# gps.net
KiCad netlist of a schematic drawn in Altium Designer
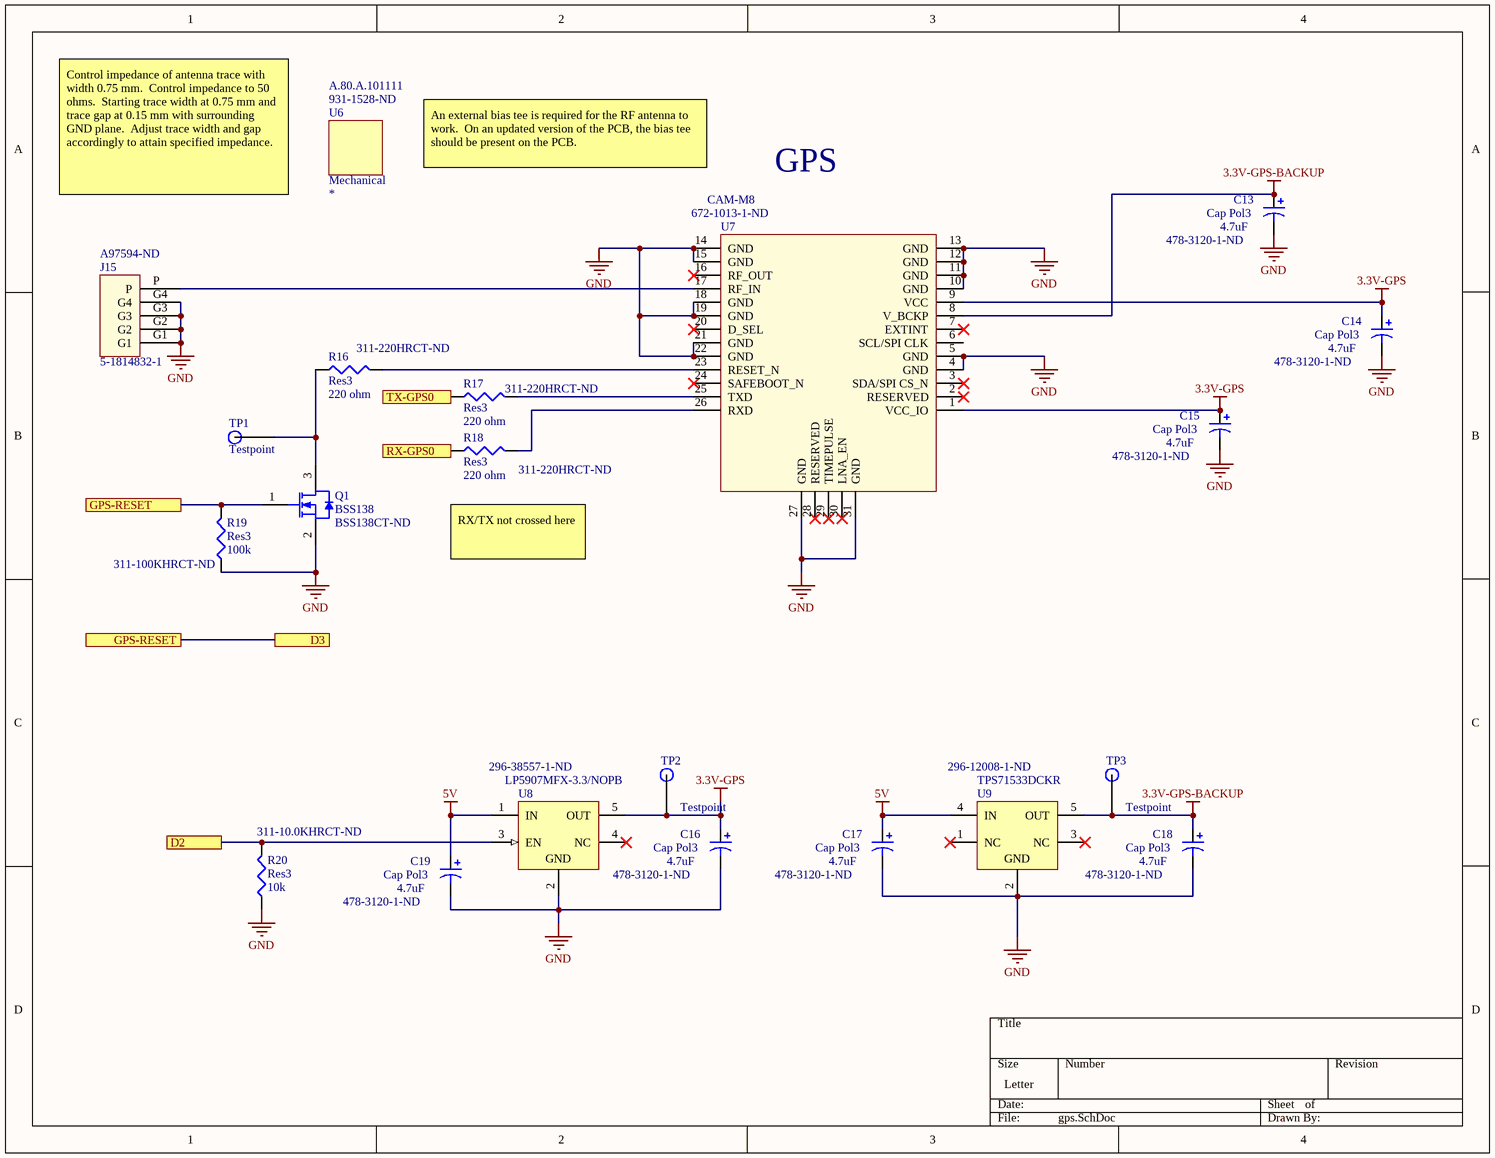
[diagram p0: gps.SchDoc]

(export (version "E")
  (design (tool "Eeschema 10.0.6"))
  (components
    (comp (ref "C13")
      (value "Cap Pol3")
      (footprint "1206-pol")
      (description "Polarized Capacitor (Surface Mount)")
      (fields
        (field (name "ALTIUM_VALUE") "4.7uF")
        (field (name "SUPPLIER PART NUMBER 1") "478-3120-1-ND")
        (field (name "MANUFACTURER") "AVX Corporation")
        (field (name "MANUFACTURER PART NUMBER") "NOJA475M010RWJ")
      )
      (libsource (lib "Miscellaneous Devices") (part "Cap Pol3"))
    )
    (comp (ref "C14")
      (value "Cap Pol3")
      (footprint "1206-pol")
      (description "Polarized Capacitor (Surface Mount)")
      (fields
        (field (name "ALTIUM_VALUE") "4.7uF")
        (field (name "SUPPLIER PART NUMBER 1") "478-3120-1-ND")
        (field (name "MANUFACTURER") "AVX Corporation")
        (field (name "MANUFACTURER PART NUMBER") "NOJA475M010RWJ")
      )
      (libsource (lib "Miscellaneous Devices") (part "Cap Pol3"))
    )
    (comp (ref "C15")
      (value "Cap Pol3")
      (footprint "1206-pol")
      (description "Polarized Capacitor (Surface Mount)")
      (fields
        (field (name "ALTIUM_VALUE") "4.7uF")
        (field (name "SUPPLIER PART NUMBER 1") "478-3120-1-ND")
        (field (name "MANUFACTURER") "AVX Corporation")
        (field (name "MANUFACTURER PART NUMBER") "NOJA475M010RWJ")
      )
      (libsource (lib "Miscellaneous Devices") (part "Cap Pol3"))
    )
    (comp (ref "C16")
      (value "Cap Pol3")
      (footprint "1206-pol")
      (description "Polarized Capacitor (Surface Mount)")
      (fields
        (field (name "ALTIUM_VALUE") "4.7uF")
        (field (name "SUPPLIER PART NUMBER 1") "478-3120-1-ND")
        (field (name "MANUFACTURER") "AVX Corporation")
        (field (name "MANUFACTURER PART NUMBER") "NOJA475M010RWJ")
      )
      (libsource (lib "Miscellaneous Devices") (part "Cap Pol3"))
    )
    (comp (ref "C17")
      (value "Cap Pol3")
      (footprint "1206-pol")
      (description "Polarized Capacitor (Surface Mount)")
      (fields
        (field (name "ALTIUM_VALUE") "4.7uF")
        (field (name "SUPPLIER PART NUMBER 1") "478-3120-1-ND")
        (field (name "MANUFACTURER") "AVX Corporation")
        (field (name "MANUFACTURER PART NUMBER") "NOJA475M010RWJ")
      )
      (libsource (lib "Miscellaneous Devices") (part "Cap Pol3"))
    )
    (comp (ref "C18")
      (value "Cap Pol3")
      (footprint "1206-pol")
      (description "Polarized Capacitor (Surface Mount)")
      (fields
        (field (name "ALTIUM_VALUE") "4.7uF")
        (field (name "SUPPLIER PART NUMBER 1") "478-3120-1-ND")
        (field (name "MANUFACTURER") "AVX Corporation")
        (field (name "MANUFACTURER PART NUMBER") "NOJA475M010RWJ")
      )
      (libsource (lib "Miscellaneous Devices") (part "Cap Pol3"))
    )
    (comp (ref "C19")
      (value "Cap Pol3")
      (footprint "1206-pol")
      (description "Polarized Capacitor (Surface Mount)")
      (fields
        (field (name "ALTIUM_VALUE") "4.7uF")
        (field (name "SUPPLIER PART NUMBER 1") "478-3120-1-ND")
        (field (name "MANUFACTURER") "AVX Corporation")
        (field (name "MANUFACTURER PART NUMBER") "NOJA475M010RWJ")
      )
      (libsource (lib "Miscellaneous Devices") (part "Cap Pol3"))
    )
    (comp (ref "J15")
      (value "5-1814832-1")
      (footprint "5-1814832-1")
      (fields
        (field (name "SUPPLIER PART NUMBER 1") "A97594-ND")
        (field (name "MANUFACTURER") "TE Connectivity")
      )
      (libsource (lib "TE") (part "5-1814832-1"))
    )
    (comp (ref "Q1")
      (value "BSS138")
      (footprint "FAIR-SOT23-3_V")
      (fields
        (field (name "TOLERANCE") "30ppm")
        (field (name "SUPPLIER PART NUMBER 1") "BSS138CT-ND")
        (field (name "MANUFACTURER") "Fairchild/ON Semiconductor")
      )
      (libsource (lib "Altium Content Vault") (part "NEMOS-GSD-3"))
    )
    (comp (ref "R16")
      (value "Res3")
      (footprint "J1-0603")
      (description "Resistor")
      (fields
        (field (name "ALTIUM_VALUE") "220 ohm")
        (field (name "SUPPLIER PART NUMBER 1") "311-220HRCT-ND")
        (field (name "MANUFACTURER") "Yageo")
        (field (name "MANUFACTURER PART NUMBER") "RC0603FR-07220RL")
        (field (name "PUBLISHER") "Altium Limited")
      )
      (libsource (lib "Miscellaneous Devices") (part "Res3"))
    )
    (comp (ref "R17")
      (value "Res3")
      (footprint "J1-0603")
      (description "Resistor")
      (fields
        (field (name "ALTIUM_VALUE") "220 ohm")
        (field (name "SUPPLIER PART NUMBER 1") "311-220HRCT-ND")
        (field (name "MANUFACTURER") "Yageo")
        (field (name "MANUFACTURER PART NUMBER") "RC0603FR-07220RL")
        (field (name "PUBLISHER") "Altium Limited")
      )
      (libsource (lib "Miscellaneous Devices") (part "Res3"))
    )
    (comp (ref "R18")
      (value "Res3")
      (footprint "J1-0603")
      (description "Resistor")
      (fields
        (field (name "ALTIUM_VALUE") "220 ohm")
        (field (name "SUPPLIER PART NUMBER 1") "311-220HRCT-ND")
        (field (name "MANUFACTURER") "Yageo")
        (field (name "MANUFACTURER PART NUMBER") "RC0603FR-07220RL")
        (field (name "PUBLISHER") "Altium Limited")
      )
      (libsource (lib "Miscellaneous Devices") (part "Res3"))
    )
    (comp (ref "R19")
      (value "Res3")
      (footprint "J1-0603")
      (description "Resistor")
      (fields
        (field (name "ALTIUM_VALUE") "100k")
        (field (name "SUPPLIER PART NUMBER 1") "311-100KHRCT-ND")
        (field (name "MANUFACTURER") "Yageo")
        (field (name "MANUFACTURER PART NUMBER") "RC0603FR-07100KL")
        (field (name "PUBLISHER") "Altium Limited")
      )
      (libsource (lib "Miscellaneous Devices") (part "Res3"))
    )
    (comp (ref "R20")
      (value "Res3")
      (footprint "J1-0603")
      (description "Resistor")
      (fields
        (field (name "ALTIUM_VALUE") "10k")
        (field (name "SUPPLIER PART NUMBER 1") "311-10.0KHRCT-ND")
        (field (name "MANUFACTURER") "Yageo")
        (field (name "MANUFACTURER PART NUMBER") "RC0603FR-0710KL")
        (field (name "PUBLISHER") "Altium Limited")
      )
      (libsource (lib "Miscellaneous Devices") (part "Res3"))
    )
    (comp (ref "TP1")
      (value "Testpoint")
      (footprint "testpoint")
      (description "SMT Testpoint")
      (libsource (lib "testpoints") (part "SMT Testpoint"))
    )
    (comp (ref "TP2")
      (value "Testpoint")
      (footprint "testpoint")
      (description "SMT Testpoint")
      (libsource (lib "testpoints") (part "SMT Testpoint"))
    )
    (comp (ref "TP3")
      (value "Testpoint")
      (footprint "testpoint")
      (description "SMT Testpoint")
      (libsource (lib "testpoints") (part "SMT Testpoint"))
    )
    (comp (ref "U6")
      (value "Mechanical")
      (description "Mechanical Part")
      (fields
        (field (name "SUPPLIER PART NUMBER 1") "*")
        (field (name "SUPPLIER PART NUMBER 2") "931-1528-ND")
        (field (name "MANUFACTURER") "Taoglas")
        (field (name "MANUFACTURER PART NUMBER") "A.80.A.101111")
      )
      (libsource (lib "mechanical") (part "Mechanical part"))
    )
    (comp (ref "U7")
      (value "CAM-M8")
      (footprint "CAM")
      (description "u-blox CAM GNSS antenna module")
      (fields
        (field (name "MANUFACTURER") "u-blox")
        (field (name "SUPPLIER PART NUMBER 1") "672-1013-1-ND")
        (field (name "MANUFACTURER PART NUMBER") "CAM-M8Q-0")
      )
      (libsource (lib "ubloxLib") (part "CAM-M8"))
    )
    (comp (ref "U8")
      (value "LP5907MFX-3.3/NOPB")
      (footprint "DBV0005A_L")
      (fields
        (field (name "MANUFACTURER") "Texas Instruments")
        (field (name "SUPPLIER PART NUMBER 1") "296-38557-1-ND")
      )
      (libsource (lib "Altium Content Vault") (part "TI-LP5907-SOT-23-5"))
    )
    (comp (ref "U9")
      (value "TPS71533DCKR")
      (footprint "DCK0005A_L")
      (fields
        (field (name "MANUFACTURER") "Texas Instruments")
        (field (name "SUPPLIER PART NUMBER 1") "296-12008-1-ND")
      )
      (libsource (lib "Altium Content Vault") (part "TI-TPS71XXXX-XXDCK5"))
    )
  )
  (nets
    (net (code "1") (name "/D2") (class "Default")
      (node (ref "R20") (pin "2") (pinfunction "2_2") (pintype "passive"))
      (node (ref "U8") (pin "3") (pinfunction "EN_3") (pintype "input"))
    )
    (net (code "2") (name "/D3") (class "Default")
      (node (ref "Q1") (pin "1") (pinfunction "G_1") (pintype "passive"))
      (node (ref "R19") (pin "2") (pinfunction "2_2") (pintype "passive"))
    )
    (net (code "3") (name "/RX-GPS0") (class "Default")
      (node (ref "R18") (pin "1") (pinfunction "1_1") (pintype "passive"))
    )
    (net (code "4") (name "/TX-GPS0") (class "Default")
      (node (ref "R17") (pin "1") (pinfunction "1_1") (pintype "passive"))
    )
    (net (code "5") (name "3.3V-GPS") (class "Default")
      (node (ref "C14") (pin "1") (pinfunction "1_1") (pintype "passive"))
      (node (ref "C15") (pin "1") (pinfunction "1_1") (pintype "passive"))
      (node (ref "C16") (pin "1") (pinfunction "1_1") (pintype "passive"))
      (node (ref "TP2") (pin "1") (pinfunction "1_1") (pintype "passive"))
      (node (ref "U7") (pin "1") (pinfunction "VCC_IO_1") (pintype "passive"))
      (node (ref "U7") (pin "9") (pinfunction "VCC_9") (pintype "passive"))
      (node (ref "U8") (pin "5") (pinfunction "OUT_5") (pintype "power_in"))
    )
    (net (code "6") (name "3.3V-GPS-BACKUP") (class "Default")
      (node (ref "C13") (pin "1") (pinfunction "1_1") (pintype "passive"))
      (node (ref "C18") (pin "1") (pinfunction "1_1") (pintype "passive"))
      (node (ref "TP3") (pin "1") (pinfunction "1_1") (pintype "passive"))
      (node (ref "U7") (pin "8") (pinfunction "V_BCKP_8") (pintype "passive"))
      (node (ref "U9") (pin "5") (pinfunction "OUT_5") (pintype "power_in"))
    )
    (net (code "7") (name "5V") (class "Default")
      (node (ref "C17") (pin "1") (pinfunction "1_1") (pintype "passive"))
      (node (ref "C19") (pin "1") (pinfunction "1_1") (pintype "passive"))
      (node (ref "U8") (pin "1") (pinfunction "IN_1") (pintype "power_in"))
      (node (ref "U9") (pin "4") (pinfunction "IN_4") (pintype "power_in"))
    )
    (net (code "8") (name "GND") (class "Default")
      (node (ref "C13") (pin "2") (pinfunction "2_2") (pintype "passive"))
      (node (ref "C14") (pin "2") (pinfunction "2_2") (pintype "passive"))
      (node (ref "C15") (pin "2") (pinfunction "2_2") (pintype "passive"))
      (node (ref "C16") (pin "2") (pinfunction "2_2") (pintype "passive"))
      (node (ref "C17") (pin "2") (pinfunction "2_2") (pintype "passive"))
      (node (ref "C18") (pin "2") (pinfunction "2_2") (pintype "passive"))
      (node (ref "C19") (pin "2") (pinfunction "2_2") (pintype "passive"))
      (node (ref "J15") (pin "G1") (pinfunction "G1_G1") (pintype "passive"))
      (node (ref "J15") (pin "G2") (pinfunction "G2_G2") (pintype "passive"))
      (node (ref "J15") (pin "G3") (pinfunction "G3_G3") (pintype "passive"))
      (node (ref "J15") (pin "G4") (pinfunction "G4_G4") (pintype "passive"))
      (node (ref "Q1") (pin "2") (pinfunction "S_2") (pintype "passive"))
      (node (ref "R19") (pin "1") (pinfunction "1_1") (pintype "passive"))
      (node (ref "R20") (pin "1") (pinfunction "1_1") (pintype "passive"))
      (node (ref "U7") (pin "10") (pinfunction "GND_10") (pintype "passive"))
      (node (ref "U7") (pin "11") (pinfunction "GND_11") (pintype "passive"))
      (node (ref "U7") (pin "12") (pinfunction "GND_12") (pintype "passive"))
      (node (ref "U7") (pin "13") (pinfunction "GND_13") (pintype "passive"))
      (node (ref "U7") (pin "14") (pinfunction "GND_14") (pintype "passive"))
      (node (ref "U7") (pin "15") (pinfunction "GND_15") (pintype "passive"))
      (node (ref "U7") (pin "18") (pinfunction "GND_18") (pintype "passive"))
      (node (ref "U7") (pin "19") (pinfunction "GND_19") (pintype "passive"))
      (node (ref "U7") (pin "21") (pinfunction "GND_21") (pintype "passive"))
      (node (ref "U7") (pin "22") (pinfunction "GND_22") (pintype "passive"))
      (node (ref "U7") (pin "27") (pinfunction "GND_27") (pintype "passive"))
      (node (ref "U7") (pin "31") (pinfunction "GND_31") (pintype "passive"))
      (node (ref "U7") (pin "4") (pinfunction "GND_4") (pintype "passive"))
      (node (ref "U7") (pin "5") (pinfunction "GND_5") (pintype "passive"))
      (node (ref "U8") (pin "2") (pinfunction "GND_2") (pintype "power_in"))
      (node (ref "U9") (pin "2") (pinfunction "GND_2") (pintype "power_in"))
    )
    (net (code "9") (name "Net-(Q1-D)") (class "Default")
      (node (ref "Q1") (pin "3") (pinfunction "D_3") (pintype "passive"))
      (node (ref "R16") (pin "1") (pinfunction "1_1") (pintype "passive"))
      (node (ref "TP1") (pin "1") (pinfunction "1_1") (pintype "passive"))
    )
    (net (code "10") (name "Net-(U7-RESET_N)") (class "Default")
      (node (ref "R16") (pin "2") (pinfunction "2_2") (pintype "passive"))
      (node (ref "U7") (pin "23") (pinfunction "RESET_N_23") (pintype "passive"))
    )
    (net (code "11") (name "Net-(U7-RF_IN)") (class "Default")
      (node (ref "J15") (pin "P") (pinfunction "P_P") (pintype "passive"))
      (node (ref "U7") (pin "17") (pinfunction "RF_IN_17") (pintype "passive"))
    )
    (net (code "12") (name "Net-(U7-RXD)") (class "Default")
      (node (ref "R18") (pin "2") (pinfunction "2_2") (pintype "passive"))
      (node (ref "U7") (pin "26") (pinfunction "RXD_26") (pintype "passive"))
    )
    (net (code "13") (name "Net-(U7-TXD)") (class "Default")
      (node (ref "R17") (pin "2") (pinfunction "2_2") (pintype "passive"))
      (node (ref "U7") (pin "25") (pinfunction "TXD_25") (pintype "passive"))
    )
    (net (code "14") (name "unconnected-(U7-D_SEL-Pad20)") (class "Default")
      (node (ref "U7") (pin "20") (pinfunction "D_SEL_20") (pintype "passive+no_connect"))
    )
    (net (code "15") (name "unconnected-(U7-EXTINT-Pad7)") (class "Default")
      (node (ref "U7") (pin "7") (pinfunction "EXTINT_7") (pintype "passive+no_connect"))
    )
    (net (code "16") (name "unconnected-(U7-LNA_EN-Pad30)") (class "Default")
      (node (ref "U7") (pin "30") (pinfunction "LNA_EN_30") (pintype "passive+no_connect"))
    )
    (net (code "17") (name "unconnected-(U7-RESERVED-Pad2)") (class "Default")
      (node (ref "U7") (pin "2") (pinfunction "RESERVED_2") (pintype "passive+no_connect"))
    )
    (net (code "18") (name "unconnected-(U7-RESERVED-Pad28)") (class "Default")
      (node (ref "U7") (pin "28") (pinfunction "RESERVED_28") (pintype "passive+no_connect"))
    )
    (net (code "19") (name "unconnected-(U7-RF_OUT-Pad16)") (class "Default")
      (node (ref "U7") (pin "16") (pinfunction "RF_OUT_16") (pintype "passive+no_connect"))
    )
    (net (code "20") (name "unconnected-(U7-SAFEBOOT_N-Pad24)") (class "Default")
      (node (ref "U7") (pin "24") (pinfunction "SAFEBOOT_N_24") (pintype "passive+no_connect"))
    )
    (net (code "21") (name "unconnected-(U7-SCL{slash}SPI_CLK-Pad6)") (class "Default")
      (node (ref "U7") (pin "6") (pinfunction "SCL/SPI_CLK_6") (pintype "passive"))
    )
    (net (code "22") (name "unconnected-(U7-SDA{slash}SPI_CS_N-Pad3)") (class "Default")
      (node (ref "U7") (pin "3") (pinfunction "SDA/SPI_CS_N_3") (pintype "passive+no_connect"))
    )
    (net (code "23") (name "unconnected-(U7-TIMEPULSE-Pad29)") (class "Default")
      (node (ref "U7") (pin "29") (pinfunction "TIMEPULSE_29") (pintype "passive+no_connect"))
    )
    (net (code "24") (name "unconnected-(U8-NC-Pad4)") (class "Default")
      (node (ref "U8") (pin "4") (pinfunction "NC_4") (pintype "passive+no_connect"))
    )
    (net (code "25") (name "unconnected-(U9-NC-Pad1)") (class "Default")
      (node (ref "U9") (pin "1") (pinfunction "NC_1") (pintype "passive+no_connect"))
    )
    (net (code "26") (name "unconnected-(U9-NC-Pad3)") (class "Default")
      (node (ref "U9") (pin "3") (pinfunction "NC_3") (pintype "passive+no_connect"))
    )
  )
)
